# MC_Project.net
KiCad netlist of a schematic drawn in Altium Designer
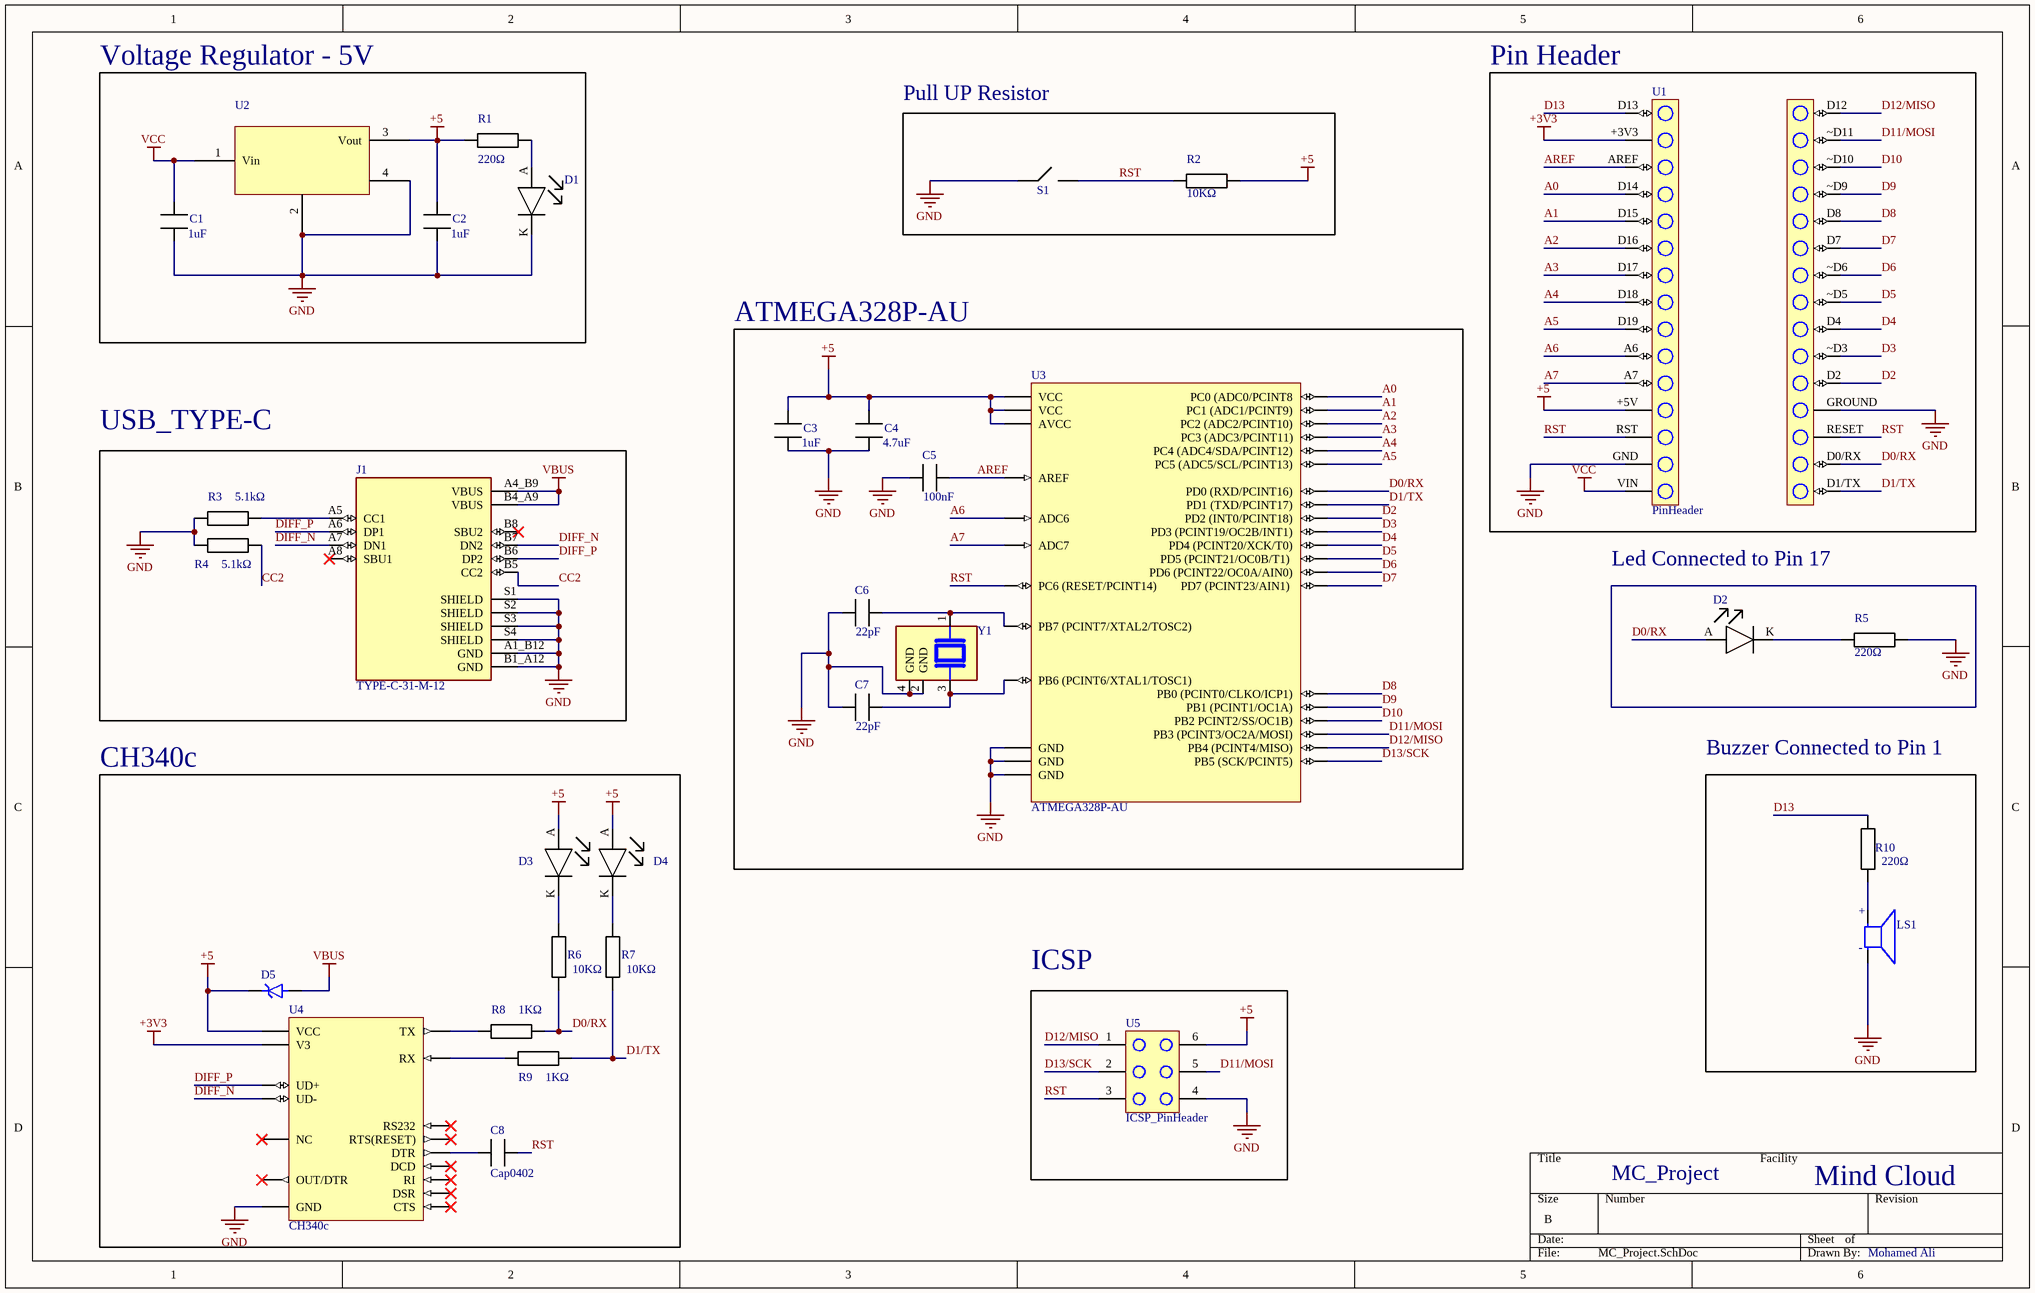
[diagram p0: MC_Project.SchDoc]

(export (version "E")
  (design (tool "Eeschema 10.0.6"))
  (components
    (comp (ref "C1")
      (value "1uF")
      (footprint "CAPC1005X06N")
      (description "Cap0402")
      (fields
        (field (name "MANUFACTURER") "Murata Electronics")
        (field (name "MANUFACTURER PART NUMBER") "GRM155R71C104KA88J")
      )
      (libsource (lib "Cap0402") (part "Cap0402"))
    )
    (comp (ref "C2")
      (value "1uF")
      (footprint "CAPC1005X06N")
      (description "Cap0402")
      (fields
        (field (name "MANUFACTURER") "Murata Electronics")
        (field (name "MANUFACTURER PART NUMBER") "GRM155R71C104KA88J")
      )
      (libsource (lib "Cap0402") (part "Cap0402"))
    )
    (comp (ref "C3")
      (value "1uF")
      (footprint "CAPC1005X06N")
      (description "Cap0402")
      (fields
        (field (name "MANUFACTURER") "Murata Electronics")
        (field (name "MANUFACTURER PART NUMBER") "GRM155R71C104KA88J")
      )
      (libsource (lib "Cap0402") (part "Cap0402"))
    )
    (comp (ref "C4")
      (value "4.7uF")
      (footprint "CAPC1005X06N")
      (description "Cap0402")
      (fields
        (field (name "MANUFACTURER") "Murata Electronics")
        (field (name "MANUFACTURER PART NUMBER") "GRM155R71C104KA88J")
      )
      (libsource (lib "Cap0402") (part "Cap0402"))
    )
    (comp (ref "C5")
      (value "100nF")
      (footprint "CAPC1005X06N")
      (description "Cap0402")
      (fields
        (field (name "MANUFACTURER") "Murata Electronics")
        (field (name "MANUFACTURER PART NUMBER") "GRM155R71C104KA88J")
      )
      (libsource (lib "Cap0402") (part "Cap0402"))
    )
    (comp (ref "C6")
      (value "22pF")
      (footprint "CAPC1005X06N")
      (description "Cap0402")
      (fields
        (field (name "MANUFACTURER") "Murata Electronics")
        (field (name "MANUFACTURER PART NUMBER") "GRM155R71C104KA88J")
      )
      (libsource (lib "Cap0402") (part "Cap0402"))
    )
    (comp (ref "C7")
      (value "22pF")
      (footprint "CAPC1005X06N")
      (description "Cap0402")
      (fields
        (field (name "MANUFACTURER") "Murata Electronics")
        (field (name "MANUFACTURER PART NUMBER") "GRM155R71C104KA88J")
      )
      (libsource (lib "Cap0402") (part "Cap0402"))
    )
    (comp (ref "C8")
      (value "Cap0402")
      (footprint "CAPC1005X06N")
      (fields
        (field (name "MANUFACTURER") "Murata Electronics")
        (field (name "MANUFACTURER PART NUMBER") "GRM155R71C104KA88J")
      )
      (libsource (lib "Cap0402") (part "Cap0402"))
    )
    (comp (ref "D1")
      (value "LED0805")
      (footprint "Led")
      (fields
        (field (name "MANUFACTURER") "Würth Elektronik")
        (field (name "MANUFACTURER PART NUMBER") "150080BS75000")
      )
      (libsource (lib "Led0805") (part "LED0805"))
    )
    (comp (ref "D2")
      (value "LED0805")
      (footprint "Led")
      (fields
        (field (name "MANUFACTURER") "Würth Elektronik")
        (field (name "MANUFACTURER PART NUMBER") "150080BS75000")
      )
      (libsource (lib "Led0805") (part "LED0805"))
    )
    (comp (ref "D3")
      (value "LED0805")
      (footprint "Led")
      (fields
        (field (name "MANUFACTURER") "Würth Elektronik")
        (field (name "MANUFACTURER PART NUMBER") "150080BS75000")
      )
      (libsource (lib "Led0805") (part "LED0805"))
    )
    (comp (ref "D4")
      (value "LED0805")
      (footprint "Led")
      (fields
        (field (name "MANUFACTURER") "Würth Elektronik")
        (field (name "MANUFACTURER PART NUMBER") "150080BS75000")
      )
      (libsource (lib "Led0805") (part "LED0805"))
    )
    (comp (ref "D5")
      (value "1SMA5926")
      (footprint "DIOM4325X250N")
      (description "DO-214AC (SMA), 1500mW, 5%, Zener Diode")
      (fields (field (name "MF") "Taiwan Semiconductor"))
      (libsource (lib "1SMA5926") (part "1SMA5926"))
    )
    (comp (ref "J1")
      (value "TYPE-C-31-M-12")
      (footprint "HRO_TYPE-C-31-M-12")
      (description "USB Connectors 24 Receptacle 1 8.94*7.3mm RoHS")
      (fields (field (name "MF") "HRO Electronics Co., Ltd."))
      (libsource (lib "TYPE-C-31-M-12") (part "TYPE-C-31-M-12"))
    )
    (comp (ref "LS1")
      (value "CMI-9705-0380-SMT-TR")
      (footprint "CUI_CMI-9705-0380-SMT-TR")
      (description "9.7 mm, 3 Vdc, 80 dB, Surface Mount, Driving Circuit, Magnetic Audio Indicator Buzzer")
      (fields
        (field (name "DIGI-KEY_PART_NUMBER") "102-CMI-9705-0380-SMT-TR-ND")
        (field (name "MF") "CUI Devices")
      )
      (libsource (lib "CMI-9705-0380-SMT-TR") (part "CMI-9705-0380-SMT-TR"))
    )
    (comp (ref "R1")
      (value "220Ω")
      (footprint "RESC1508X03N")
      (description "Resistance-0603")
      (fields
        (field (name "MANUFACTURER") "YAGEO")
        (field (name "MANUFACTURER PART NUMBER") "RC0603FR-0710KL")
      )
      (libsource (lib "Resistance0603") (part "Resistance-0603"))
    )
    (comp (ref "R2")
      (value "10KΩ")
      (footprint "RESC1508X03N")
      (description "Resistance-0603")
      (fields
        (field (name "MANUFACTURER") "YAGEO")
        (field (name "MANUFACTURER PART NUMBER") "RC0603FR-0710KL")
      )
      (libsource (lib "Resistance0603") (part "Resistance-0603"))
    )
    (comp (ref "R3")
      (value "5.1kΩ")
      (footprint "RESC1508X03N")
      (description "Resistance-0603")
      (fields
        (field (name "MANUFACTURER") "YAGEO")
        (field (name "MANUFACTURER PART NUMBER") "RC0603FR-0710KL")
      )
      (libsource (lib "Resistance0603") (part "Resistance-0603"))
    )
    (comp (ref "R4")
      (value "5.1kΩ")
      (footprint "RESC1508X03N")
      (description "Resistance-0603")
      (fields
        (field (name "MANUFACTURER") "YAGEO")
        (field (name "MANUFACTURER PART NUMBER") "RC0603FR-0710KL")
      )
      (libsource (lib "Resistance0603") (part "Resistance-0603"))
    )
    (comp (ref "R5")
      (value "220Ω")
      (footprint "RESC1508X03N")
      (description "Resistance-0603")
      (fields
        (field (name "MANUFACTURER") "YAGEO")
        (field (name "MANUFACTURER PART NUMBER") "RC0603FR-0710KL")
      )
      (libsource (lib "Resistance0603") (part "Resistance-0603"))
    )
    (comp (ref "R6")
      (value "10KΩ")
      (footprint "RESC1508X03N")
      (description "Resistance-0603")
      (fields
        (field (name "MANUFACTURER") "YAGEO")
        (field (name "MANUFACTURER PART NUMBER") "RC0603FR-0710KL")
      )
      (libsource (lib "Resistance0603") (part "Resistance-0603"))
    )
    (comp (ref "R7")
      (value "10KΩ")
      (footprint "RESC1508X03N")
      (description "Resistance-0603")
      (fields
        (field (name "MANUFACTURER") "YAGEO")
        (field (name "MANUFACTURER PART NUMBER") "RC0603FR-0710KL")
      )
      (libsource (lib "Resistance0603") (part "Resistance-0603"))
    )
    (comp (ref "R8")
      (value "1KΩ")
      (footprint "RESC1508X03N")
      (description "Resistance-0603")
      (fields
        (field (name "MANUFACTURER") "YAGEO")
        (field (name "MANUFACTURER PART NUMBER") "RC0603FR-0710KL")
      )
      (libsource (lib "Resistance0603") (part "Resistance-0603"))
    )
    (comp (ref "R9")
      (value "1KΩ")
      (footprint "RESC1508X03N")
      (description "Resistance-0603")
      (fields
        (field (name "MANUFACTURER") "YAGEO")
        (field (name "MANUFACTURER PART NUMBER") "RC0603FR-0710KL")
      )
      (libsource (lib "Resistance0603") (part "Resistance-0603"))
    )
    (comp (ref "R10")
      (value "220Ω")
      (footprint "RESC1508X03N")
      (description "Resistance-0603")
      (fields
        (field (name "MANUFACTURER") "YAGEO")
        (field (name "MANUFACTURER PART NUMBER") "RC0603FR-0710KL")
      )
      (libsource (lib "Resistance0603") (part "Resistance-0603"))
    )
    (comp (ref "S1")
      (value "Switch")
      (footprint "Switch - duplicate")
      (fields
        (field (name "MANUFACTURER") "Alps Alpine")
        (field (name "MANUFACTURER PART NUMBER") "SKRPACE010")
      )
      (libsource (lib "Switch") (part "Switch"))
    )
    (comp (ref "U1")
      (value "PinHeader")
      (footprint "PCBComponent_1")
      (libsource (lib "PinHeader") (part "PinHeader"))
    )
    (comp (ref "U2")
      (value "LM7805")
      (footprint "LM7805-SOT223")
      (fields
        (field (name "MANUFACTURER") "Texas Instruments")
        (field (name "MANUFACTURER PART NUMBER") "LM7805/NOPB")
      )
      (libsource (lib "LM7805") (part "LM7805"))
    )
    (comp (ref "U3")
      (value "ATMEGA328P-AU")
      (footprint "ATMEGA328P-AU")
      (fields (field (name "MANUFACTURER") "Microchip Technology"))
      (libsource (lib "ATMEGA328P-AU") (part "ATMEGA328P-AU"))
    )
    (comp (ref "U4")
      (value "CH340c")
      (footprint "CH340c")
      (fields
        (field (name "MANUFACTURER") "WCH(Jiangsu Qin Heng)")
        (field (name "MANUFACTURER PART NUMBER") "CH340C-SSOP16")
      )
      (libsource (lib "CH340c") (part "CH340c"))
    )
    (comp (ref "U5")
      (value "ICSP_PinHeader")
      (footprint "Edge Connector")
      (fields
        (field (name "MANUFACTURER") "TE Connectivity AMP Connectors")
        (field (name "MANUFACTURER PART NUMBER") "4-103321-0")
      )
      (libsource (lib "ICSP-PinHeader") (part "ICSP_PinHeader"))
    )
    (comp (ref "Y1")
      (value "ABM3B-16.000MHZ-B2-T")
      (footprint "XTAL_ABM3B-16.000MHZ-B2-T")
      (description "16 MHz Â±20ppm Crystal 18pF 50 Ohms 4-SMD, No Lead")
      (fields (field (name "MF") "Abracon"))
      (libsource (lib "ABM3B-16.000MHZ-B2-T") (part "ABM3B-16.000MHZ-B2-T"))
    )
  )
  (nets
    (net (code "1") (name "+3V3") (class "Default")
      (node (ref "U1") (pin "+3V3") (pinfunction "2_+3V3") (pintype "power_in"))
      (node (ref "U4") (pin "4") (pinfunction "V3_4") (pintype "power_in"))
    )
    (net (code "2") (name "+5") (class "Default")
      (node (ref "C2") (pin "2") (pinfunction "2_2") (pintype "passive"))
      (node (ref "C3") (pin "2") (pinfunction "2_2") (pintype "passive"))
      (node (ref "C4") (pin "2") (pinfunction "2_2") (pintype "passive"))
      (node (ref "D3") (pin "A") (pintype "passive"))
      (node (ref "D4") (pin "A") (pintype "passive"))
      (node (ref "D5") (pin "C") (pinfunction "K_C") (pintype "passive"))
      (node (ref "R1") (pin "1") (pinfunction "1_1") (pintype "passive"))
      (node (ref "R2") (pin "2") (pinfunction "1_2") (pintype "passive"))
      (node (ref "U1") (pin "+5V") (pinfunction "11_+5V") (pintype "power_in"))
      (node (ref "U2") (pin "3") (pinfunction "Vout_3") (pintype "passive"))
      (node (ref "U3") (pin "18") (pinfunction "AVCC_18") (pintype "power_in"))
      (node (ref "U3") (pin "4") (pinfunction "VCC_4") (pintype "power_in"))
      (node (ref "U3") (pin "6") (pinfunction "VCC_6") (pintype "power_in"))
      (node (ref "U4") (pin "16") (pinfunction "VCC_16") (pintype "power_in"))
      (node (ref "U5") (pin "6") (pinfunction "4_6") (pintype "passive"))
    )
    (net (code "3") (name "/A0") (class "Default")
      (node (ref "U1") (pin "D14") (pinfunction "3_D14") (pintype "bidirectional"))
      (node (ref "U3") (pin "23") (pinfunction "PC0_(ADC0/PCINT8_23") (pintype "bidirectional"))
    )
    (net (code "4") (name "/A1") (class "Default")
      (node (ref "U1") (pin "D15") (pinfunction "4_D15") (pintype "bidirectional"))
      (node (ref "U3") (pin "24") (pinfunction "PC1_(ADC1/PCINT9)_24") (pintype "bidirectional"))
    )
    (net (code "5") (name "/A2") (class "Default")
      (node (ref "U1") (pin "D16") (pinfunction "5_D16") (pintype "bidirectional"))
      (node (ref "U3") (pin "25") (pinfunction "PC2_(ADC2/PCINT10)_25") (pintype "bidirectional"))
    )
    (net (code "6") (name "/A3") (class "Default")
      (node (ref "U1") (pin "D17") (pinfunction "6_D17") (pintype "bidirectional"))
      (node (ref "U3") (pin "26") (pinfunction "PC3_(ADC3/PCINT11)_26") (pintype "bidirectional"))
    )
    (net (code "7") (name "/A4") (class "Default")
      (node (ref "U1") (pin "D18") (pinfunction "7_D18") (pintype "bidirectional"))
      (node (ref "U3") (pin "27") (pinfunction "PC4_(ADC4/SDA/PCINT12)_27") (pintype "bidirectional"))
    )
    (net (code "8") (name "/A5") (class "Default")
      (node (ref "U1") (pin "D19") (pinfunction "8_D19") (pintype "bidirectional"))
      (node (ref "U3") (pin "28") (pinfunction "PC5_(ADC5/SCL/PCINT13)_28") (pintype "bidirectional"))
    )
    (net (code "9") (name "/A6") (class "Default")
      (node (ref "U1") (pin "A6") (pinfunction "9_A6") (pintype "bidirectional"))
      (node (ref "U3") (pin "19") (pinfunction "ADC6_19") (pintype "input"))
    )
    (net (code "10") (name "/A7") (class "Default")
      (node (ref "U1") (pin "A7") (pinfunction "10_A7") (pintype "bidirectional"))
      (node (ref "U3") (pin "22") (pinfunction "ADC7_22") (pintype "input"))
    )
    (net (code "11") (name "/AREF") (class "Default")
      (node (ref "C5") (pin "2") (pinfunction "2_2") (pintype "passive"))
      (node (ref "U1") (pin "AREF") (pintype "bidirectional"))
      (node (ref "U3") (pin "20") (pinfunction "AREF_20") (pintype "input"))
    )
    (net (code "12") (name "/CC2") (class "Default")
      (node (ref "J1") (pin "B5") (pinfunction "CC2_B5") (pintype "bidirectional"))
      (node (ref "R4") (pin "2") (pinfunction "1_2") (pintype "passive"))
    )
    (net (code "13") (name "/D0{slash}RX") (class "Default")
      (node (ref "D2") (pin "A") (pintype "passive"))
      (node (ref "R6") (pin "1") (pinfunction "1_1") (pintype "passive"))
      (node (ref "R8") (pin "2") (pinfunction "1_2") (pintype "passive"))
      (node (ref "U1") (pin "D0/RX") (pinfunction "29_D0/RX") (pintype "bidirectional"))
      (node (ref "U3") (pin "30") (pinfunction "PD0_(RXD/PCINT16)_30") (pintype "bidirectional"))
    )
    (net (code "14") (name "/D1{slash}TX") (class "Default")
      (node (ref "R7") (pin "1") (pinfunction "1_1") (pintype "passive"))
      (node (ref "R9") (pin "2") (pinfunction "1_2") (pintype "passive"))
      (node (ref "U1") (pin "D1/TX") (pinfunction "30_D1/TX") (pintype "bidirectional"))
      (node (ref "U3") (pin "31") (pinfunction "PD1_(TXD/PCINT17)_31") (pintype "bidirectional"))
    )
    (net (code "15") (name "/D2") (class "Default")
      (node (ref "U1") (pin "D2") (pinfunction "26_D2") (pintype "bidirectional"))
      (node (ref "U3") (pin "32") (pinfunction "PD2_(INT0/PCINT18)_32") (pintype "bidirectional"))
    )
    (net (code "16") (name "/D3") (class "Default")
      (node (ref "U1") (pin "~D3") (pinfunction "25_~D3") (pintype "bidirectional"))
      (node (ref "U3") (pin "1") (pinfunction "PD3_(PCINT19/OC2B/INT1)_1") (pintype "bidirectional"))
    )
    (net (code "17") (name "/D4") (class "Default")
      (node (ref "U1") (pin "D4") (pinfunction "24_D4") (pintype "bidirectional"))
      (node (ref "U3") (pin "2") (pinfunction "PD4_(PCINT20/XCK/T0)_2") (pintype "bidirectional"))
    )
    (net (code "18") (name "/D5") (class "Default")
      (node (ref "U1") (pin "~D5") (pinfunction "23_~D5") (pintype "bidirectional"))
      (node (ref "U3") (pin "9") (pinfunction "PD5_(PCINT21/OC0B/T1)_9") (pintype "bidirectional"))
    )
    (net (code "19") (name "/D6") (class "Default")
      (node (ref "U1") (pin "~D6") (pinfunction "22_~D6") (pintype "bidirectional"))
      (node (ref "U3") (pin "10") (pinfunction "PD6_(PCINT22/OC0A/AIN0)_10") (pintype "bidirectional"))
    )
    (net (code "20") (name "/D7") (class "Default")
      (node (ref "U1") (pin "D7") (pinfunction "21_D7") (pintype "bidirectional"))
      (node (ref "U3") (pin "11") (pinfunction "PD7_(PCINT23/AIN1)_11") (pintype "bidirectional"))
    )
    (net (code "21") (name "/D8") (class "Default")
      (node (ref "U1") (pin "D8") (pinfunction "20_D8") (pintype "bidirectional"))
      (node (ref "U3") (pin "12") (pinfunction "PB0_(PCINT0/CLKO/ICP1)_12") (pintype "bidirectional"))
    )
    (net (code "22") (name "/D9") (class "Default")
      (node (ref "U1") (pin "~D9") (pinfunction "19_~D9") (pintype "bidirectional"))
      (node (ref "U3") (pin "13") (pinfunction "PB1_(PCINT1/OC1A)_13") (pintype "bidirectional"))
    )
    (net (code "23") (name "/D10") (class "Default")
      (node (ref "U1") (pin "~D10") (pinfunction "18_~D10") (pintype "bidirectional"))
      (node (ref "U3") (pin "14") (pinfunction "PB2_PCINT2/SS/OC1B)_14") (pintype "bidirectional"))
    )
    (net (code "24") (name "/D11{slash}MOSI") (class "Default")
      (node (ref "U1") (pin "~D11") (pinfunction "17_~D11") (pintype "bidirectional"))
      (node (ref "U3") (pin "15") (pinfunction "PB3_(PCINT3/OC2A/MOSI)_15") (pintype "bidirectional"))
      (node (ref "U5") (pin "5") (pintype "passive"))
    )
    (net (code "25") (name "/D12{slash}MISO") (class "Default")
      (node (ref "U1") (pin "D12") (pinfunction "16_D12") (pintype "bidirectional"))
      (node (ref "U3") (pin "16") (pinfunction "PB4_(PCINT4/MISO)_16") (pintype "bidirectional"))
      (node (ref "U5") (pin "1") (pintype "passive"))
    )
    (net (code "26") (name "/D13") (class "Default")
      (node (ref "R10") (pin "2") (pinfunction "1_2") (pintype "passive"))
      (node (ref "U1") (pin "D13") (pinfunction "1_D13") (pintype "bidirectional"))
    )
    (net (code "27") (name "/D13{slash}SCK") (class "Default")
      (node (ref "U3") (pin "17") (pinfunction "PB5_(SCK/PCINT5)_17") (pintype "bidirectional"))
      (node (ref "U5") (pin "2") (pintype "passive"))
    )
    (net (code "28") (name "/DIFF_N") (class "Default")
      (node (ref "J1") (pin "A7") (pinfunction "DN1_A7") (pintype "bidirectional"))
      (node (ref "J1") (pin "B7") (pinfunction "DN2_B7") (pintype "bidirectional"))
      (node (ref "U4") (pin "6") (pinfunction "UD-_6") (pintype "bidirectional"))
    )
    (net (code "29") (name "/DIFF_P") (class "Default")
      (node (ref "J1") (pin "A6") (pinfunction "DP1_A6") (pintype "bidirectional"))
      (node (ref "J1") (pin "B6") (pinfunction "DP2_B6") (pintype "bidirectional"))
      (node (ref "U4") (pin "5") (pinfunction "UD+_5") (pintype "bidirectional"))
    )
    (net (code "30") (name "/RST") (class "Default")
      (node (ref "C8") (pin "2") (pinfunction "2_2") (pintype "passive"))
      (node (ref "R2") (pin "1") (pinfunction "1_1") (pintype "passive"))
      (node (ref "S1") (pin "2") (pintype "passive"))
      (node (ref "U1") (pin "RESET") (pinfunction "28_RESET") (pintype "power_in"))
      (node (ref "U1") (pin "RST") (pinfunction "12_RST") (pintype "power_in"))
      (node (ref "U3") (pin "29") (pinfunction "PC6_(RESET/PCINT14)_29") (pintype "bidirectional"))
      (node (ref "U5") (pin "3") (pinfunction "3_3") (pintype "passive"))
    )
    (net (code "31") (name "GND") (class "Default")
      (node (ref "C1") (pin "1") (pinfunction "1_1") (pintype "passive"))
      (node (ref "C2") (pin "1") (pinfunction "1_1") (pintype "passive"))
      (node (ref "C3") (pin "1") (pinfunction "1_1") (pintype "passive"))
      (node (ref "C4") (pin "1") (pinfunction "1_1") (pintype "passive"))
      (node (ref "C5") (pin "1") (pinfunction "1_1") (pintype "passive"))
      (node (ref "C6") (pin "1") (pinfunction "1_1") (pintype "passive"))
      (node (ref "C7") (pin "1") (pinfunction "1_1") (pintype "passive"))
      (node (ref "D1") (pin "K") (pintype "passive"))
      (node (ref "J1") (pin "A1_B12") (pinfunction "GND_A1_B12") (pintype "power_in"))
      (node (ref "J1") (pin "B1_A12") (pinfunction "GND_B1_A12") (pintype "power_in"))
      (node (ref "J1") (pin "S1") (pinfunction "SHIELD_S1") (pintype "passive"))
      (node (ref "J1") (pin "S2") (pinfunction "SHIELD_S2") (pintype "passive"))
      (node (ref "J1") (pin "S3") (pinfunction "SHIELD_S3") (pintype "passive"))
      (node (ref "J1") (pin "S4") (pinfunction "SHIELD_S4") (pintype "passive"))
      (node (ref "LS1") (pin "N") (pinfunction "N_N") (pintype "passive"))
      (node (ref "R3") (pin "1") (pinfunction "1_1") (pintype "passive"))
      (node (ref "R4") (pin "1") (pinfunction "1_1") (pintype "passive"))
      (node (ref "R5") (pin "2") (pinfunction "1_2") (pintype "passive"))
      (node (ref "S1") (pin "1") (pintype "passive"))
      (node (ref "U1") (pin "GND") (pinfunction "13_GND") (pintype "power_in"))
      (node (ref "U1") (pin "GROUND") (pinfunction "27_GROUND") (pintype "power_in"))
      (node (ref "U2") (pin "2") (pinfunction "Common_2") (pintype "passive"))
      (node (ref "U2") (pin "4") (pinfunction "Common_4") (pintype "passive"))
      (node (ref "U3") (pin "21") (pinfunction "GND_21") (pintype "passive"))
      (node (ref "U3") (pin "3") (pinfunction "GND_3") (pintype "power_in"))
      (node (ref "U3") (pin "5") (pinfunction "GND_5") (pintype "power_in"))
      (node (ref "U4") (pin "1") (pinfunction "GND_1") (pintype "power_in"))
      (node (ref "U5") (pin "4") (pinfunction "6_4") (pintype "passive"))
      (node (ref "Y1") (pin "2") (pinfunction "GND_2") (pintype "power_in"))
      (node (ref "Y1") (pin "4") (pinfunction "GND_4") (pintype "power_in"))
    )
    (net (code "32") (name "Net-(D1-PadA)") (class "Default")
      (node (ref "D1") (pin "A") (pintype "passive"))
      (node (ref "R1") (pin "2") (pinfunction "1_2") (pintype "passive"))
    )
    (net (code "33") (name "Net-(D2-PadK)") (class "Default")
      (node (ref "D2") (pin "K") (pintype "passive"))
      (node (ref "R5") (pin "1") (pinfunction "1_1") (pintype "passive"))
    )
    (net (code "34") (name "Net-(D3-PadK)") (class "Default")
      (node (ref "D3") (pin "K") (pintype "passive"))
      (node (ref "R6") (pin "2") (pinfunction "1_2") (pintype "passive"))
    )
    (net (code "35") (name "Net-(D4-PadK)") (class "Default")
      (node (ref "D4") (pin "K") (pintype "passive"))
      (node (ref "R7") (pin "2") (pinfunction "1_2") (pintype "passive"))
    )
    (net (code "36") (name "Net-(J1-CC1)") (class "Default")
      (node (ref "J1") (pin "A5") (pinfunction "CC1_A5") (pintype "bidirectional"))
      (node (ref "R3") (pin "2") (pinfunction "1_2") (pintype "passive"))
    )
    (net (code "37") (name "Net-(LS1-PadP)") (class "Default")
      (node (ref "LS1") (pin "P") (pinfunction "P_P") (pintype "passive"))
      (node (ref "R10") (pin "1") (pinfunction "1_1") (pintype "passive"))
    )
    (net (code "38") (name "Net-(U3-PB6_(PCINT6{slash}XTAL1{slash}TOSC1))") (class "Default")
      (node (ref "C7") (pin "2") (pinfunction "2_2") (pintype "passive"))
      (node (ref "U3") (pin "7") (pinfunction "PB6_(PCINT6/XTAL1/TOSC1)_7") (pintype "bidirectional"))
      (node (ref "Y1") (pin "3") (pinfunction "2_3") (pintype "passive"))
    )
    (net (code "39") (name "Net-(U3-PB7_(PCINT7{slash}XTAL2{slash}TOSC2))") (class "Default")
      (node (ref "C6") (pin "2") (pinfunction "2_2") (pintype "passive"))
      (node (ref "U3") (pin "8") (pinfunction "PB7_(PCINT7/XTAL2/TOSC2)_8") (pintype "bidirectional"))
      (node (ref "Y1") (pin "1") (pinfunction "1_1") (pintype "passive"))
    )
    (net (code "40") (name "Net-(U4-DTR)") (class "Default")
      (node (ref "C8") (pin "1") (pinfunction "1_1") (pintype "passive"))
      (node (ref "U4") (pin "13") (pinfunction "DTR_13") (pintype "output"))
    )
    (net (code "41") (name "Net-(U4-RX)") (class "Default")
      (node (ref "R9") (pin "1") (pinfunction "1_1") (pintype "passive"))
      (node (ref "U4") (pin "3") (pinfunction "RX_3") (pintype "input"))
    )
    (net (code "42") (name "Net-(U4-TX)") (class "Default")
      (node (ref "R8") (pin "1") (pinfunction "1_1") (pintype "passive"))
      (node (ref "U4") (pin "2") (pinfunction "TX_2") (pintype "output"))
    )
    (net (code "43") (name "VBUS") (class "Default")
      (node (ref "D5") (pin "A") (pinfunction "A_A") (pintype "passive"))
      (node (ref "J1") (pin "A4_B9") (pinfunction "VBUS_A4_B9") (pintype "power_in"))
      (node (ref "J1") (pin "B4_A9") (pinfunction "VBUS_B4_A9") (pintype "power_in"))
    )
    (net (code "44") (name "VCC") (class "Default")
      (node (ref "C1") (pin "2") (pinfunction "2_2") (pintype "passive"))
      (node (ref "U1") (pin "VIN") (pinfunction "14_VIN") (pintype "power_in"))
      (node (ref "U2") (pin "1") (pinfunction "Vin_1") (pintype "passive"))
    )
    (net (code "45") (name "unconnected-(J1-SBU1-PadA8)") (class "Default")
      (node (ref "J1") (pin "A8") (pinfunction "SBU1_A8") (pintype "bidirectional+no_connect"))
    )
    (net (code "46") (name "unconnected-(J1-SBU2-PadB8)") (class "Default")
      (node (ref "J1") (pin "B8") (pinfunction "SBU2_B8") (pintype "bidirectional+no_connect"))
    )
    (net (code "47") (name "unconnected-(U4-CTS-Pad9)") (class "Default")
      (node (ref "U4") (pin "9") (pinfunction "CTS_9") (pintype "input+no_connect"))
    )
    (net (code "48") (name "unconnected-(U4-DCD-Pad12)") (class "Default")
      (node (ref "U4") (pin "12") (pinfunction "DCD_12") (pintype "input+no_connect"))
    )
    (net (code "49") (name "unconnected-(U4-DSR-Pad10)") (class "Default")
      (node (ref "U4") (pin "10") (pinfunction "DSR_10") (pintype "input+no_connect"))
    )
    (net (code "50") (name "unconnected-(U4-NC-Pad7)") (class "Default")
      (node (ref "U4") (pin "7") (pinfunction "NC_7") (pintype "passive+no_connect"))
    )
    (net (code "51") (name "unconnected-(U4-OUT{slash}DTR-Pad8)") (class "Default")
      (node (ref "U4") (pin "8") (pinfunction "OUT/DTR_8") (pintype "output+no_connect"))
    )
    (net (code "52") (name "unconnected-(U4-RI-Pad11)") (class "Default")
      (node (ref "U4") (pin "11") (pinfunction "RI_11") (pintype "input+no_connect"))
    )
    (net (code "53") (name "unconnected-(U4-RS232-Pad15)") (class "Default")
      (node (ref "U4") (pin "15") (pinfunction "RS232_15") (pintype "input+no_connect"))
    )
    (net (code "54") (name "unconnected-(U4-RTS(RESET)-Pad14)") (class "Default")
      (node (ref "U4") (pin "14") (pinfunction "RTS(RESET)_14") (pintype "output+no_connect"))
    )
  )
)
